# 5-de-7.net
KiCad netlist of a schematic drawn in EAGLE
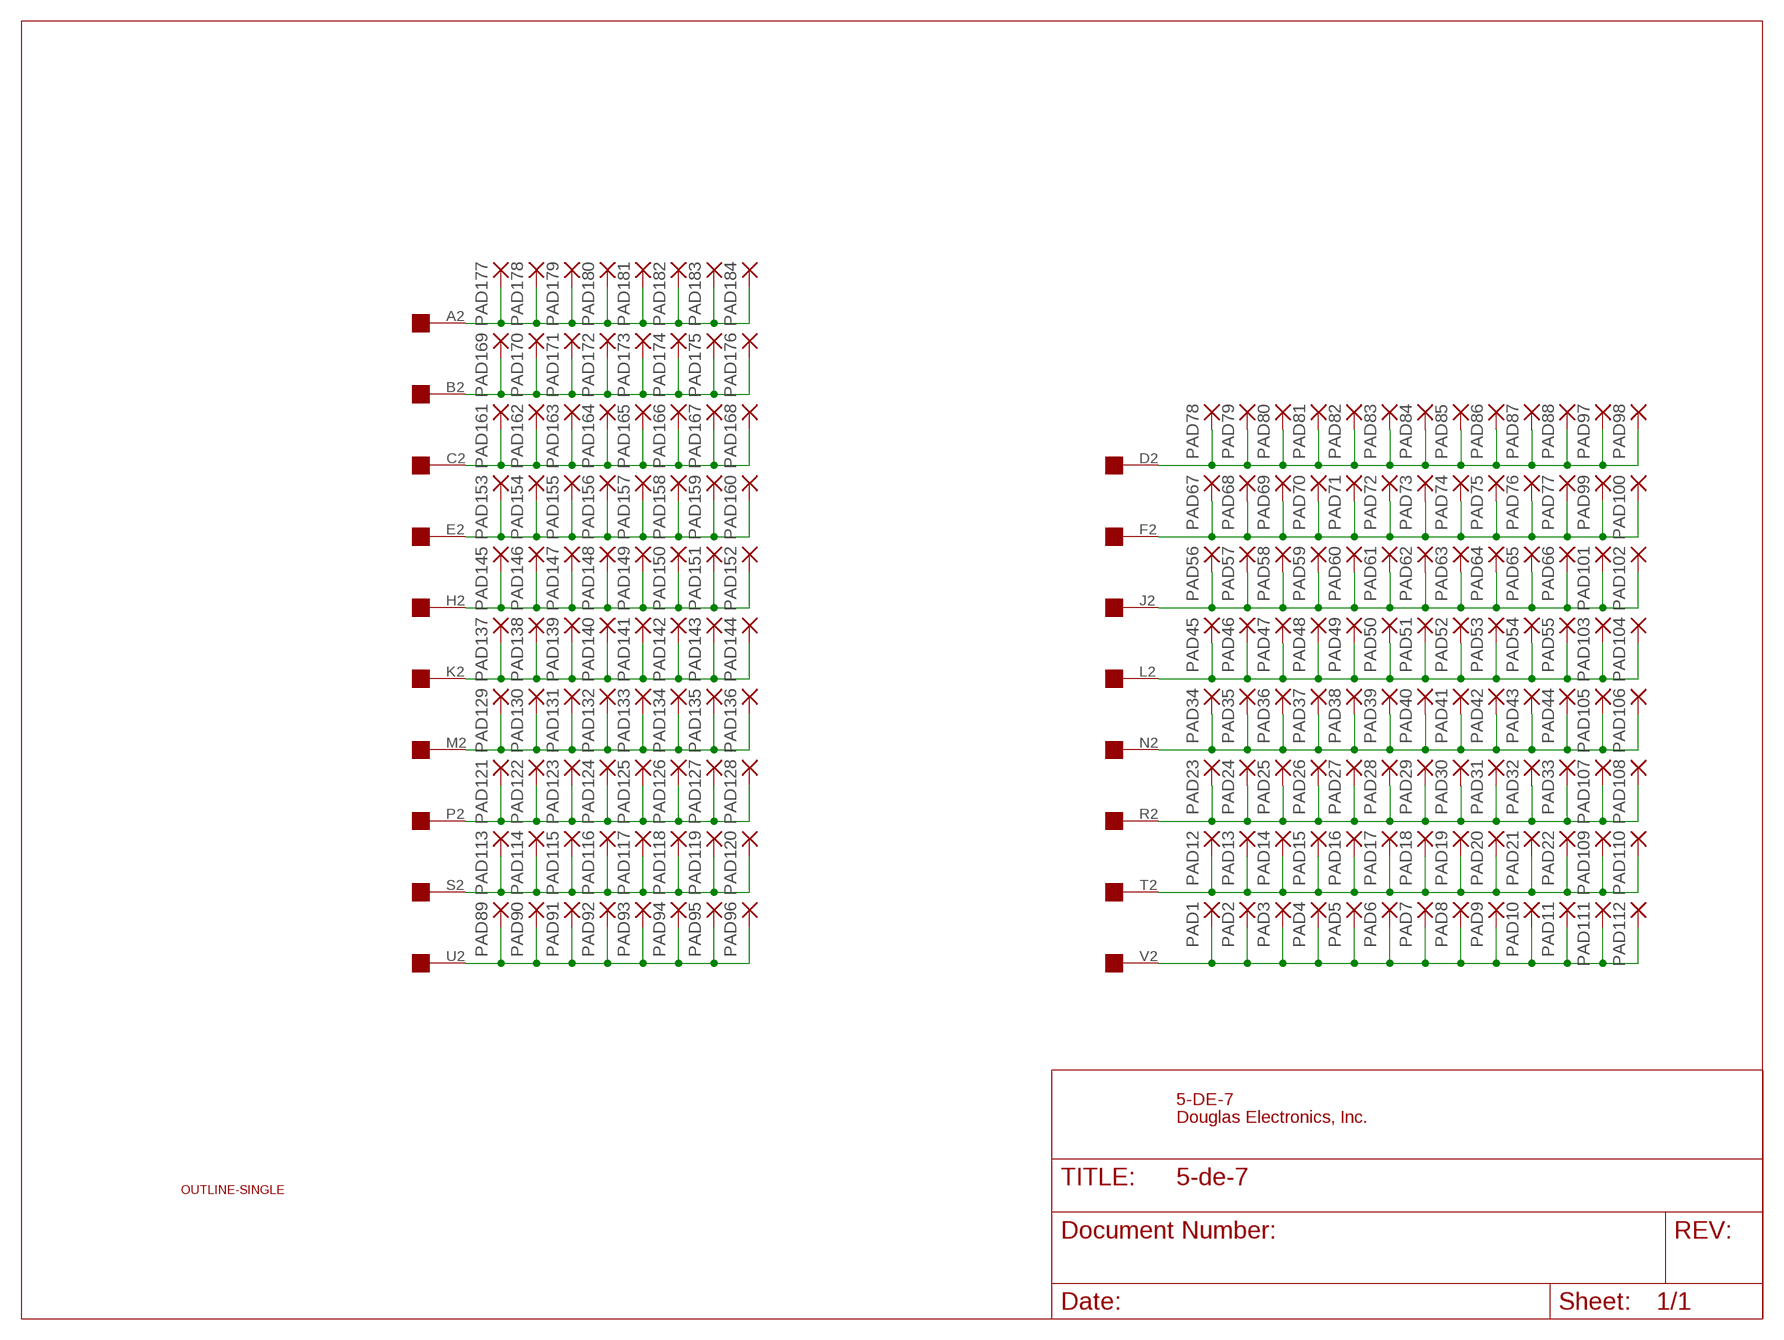
[diagram p0: schematic, sheet 1]

(export (version "E")
  (design (tool "Eeschema 10.0.6"))
  (components
    (comp (ref "PAD1")
      (value "2,54/1,1")
      (footprint "eagle-import:2,54_1,1")
      (libsource (lib "eagle-import") (part "2,54/1,1"))
    )
    (comp (ref "PAD2")
      (value "2,54/1,1")
      (footprint "eagle-import:2,54_1,1")
      (libsource (lib "eagle-import") (part "2,54/1,1"))
    )
    (comp (ref "PAD3")
      (value "2,54/1,1")
      (footprint "eagle-import:2,54_1,1")
      (libsource (lib "eagle-import") (part "2,54/1,1"))
    )
    (comp (ref "PAD4")
      (value "2,54/1,1")
      (footprint "eagle-import:2,54_1,1")
      (libsource (lib "eagle-import") (part "2,54/1,1"))
    )
    (comp (ref "PAD5")
      (value "2,54/1,1")
      (footprint "eagle-import:2,54_1,1")
      (libsource (lib "eagle-import") (part "2,54/1,1"))
    )
    (comp (ref "PAD6")
      (value "2,54/1,1")
      (footprint "eagle-import:2,54_1,1")
      (libsource (lib "eagle-import") (part "2,54/1,1"))
    )
    (comp (ref "PAD7")
      (value "2,54/1,1")
      (footprint "eagle-import:2,54_1,1")
      (libsource (lib "eagle-import") (part "2,54/1,1"))
    )
    (comp (ref "PAD8")
      (value "2,54/1,1")
      (footprint "eagle-import:2,54_1,1")
      (libsource (lib "eagle-import") (part "2,54/1,1"))
    )
    (comp (ref "PAD9")
      (value "2,54/1,1")
      (footprint "eagle-import:2,54_1,1")
      (libsource (lib "eagle-import") (part "2,54/1,1"))
    )
    (comp (ref "PAD10")
      (value "2,54/1,1")
      (footprint "eagle-import:2,54_1,1")
      (libsource (lib "eagle-import") (part "2,54/1,1"))
    )
    (comp (ref "PAD11")
      (value "2,54/1,1")
      (footprint "eagle-import:2,54_1,1")
      (libsource (lib "eagle-import") (part "2,54/1,1"))
    )
    (comp (ref "PAD12")
      (value "2,54/1,1")
      (footprint "eagle-import:2,54_1,1")
      (libsource (lib "eagle-import") (part "2,54/1,1"))
    )
    (comp (ref "PAD13")
      (value "2,54/1,1")
      (footprint "eagle-import:2,54_1,1")
      (libsource (lib "eagle-import") (part "2,54/1,1"))
    )
    (comp (ref "PAD14")
      (value "2,54/1,1")
      (footprint "eagle-import:2,54_1,1")
      (libsource (lib "eagle-import") (part "2,54/1,1"))
    )
    (comp (ref "PAD15")
      (value "2,54/1,1")
      (footprint "eagle-import:2,54_1,1")
      (libsource (lib "eagle-import") (part "2,54/1,1"))
    )
    (comp (ref "PAD16")
      (value "2,54/1,1")
      (footprint "eagle-import:2,54_1,1")
      (libsource (lib "eagle-import") (part "2,54/1,1"))
    )
    (comp (ref "PAD17")
      (value "2,54/1,1")
      (footprint "eagle-import:2,54_1,1")
      (libsource (lib "eagle-import") (part "2,54/1,1"))
    )
    (comp (ref "PAD18")
      (value "2,54/1,1")
      (footprint "eagle-import:2,54_1,1")
      (libsource (lib "eagle-import") (part "2,54/1,1"))
    )
    (comp (ref "PAD19")
      (value "2,54/1,1")
      (footprint "eagle-import:2,54_1,1")
      (libsource (lib "eagle-import") (part "2,54/1,1"))
    )
    (comp (ref "PAD20")
      (value "2,54/1,1")
      (footprint "eagle-import:2,54_1,1")
      (libsource (lib "eagle-import") (part "2,54/1,1"))
    )
    (comp (ref "PAD21")
      (value "2,54/1,1")
      (footprint "eagle-import:2,54_1,1")
      (libsource (lib "eagle-import") (part "2,54/1,1"))
    )
    (comp (ref "PAD22")
      (value "2,54/1,1")
      (footprint "eagle-import:2,54_1,1")
      (libsource (lib "eagle-import") (part "2,54/1,1"))
    )
    (comp (ref "PAD23")
      (value "2,54/1,1")
      (footprint "eagle-import:2,54_1,1")
      (libsource (lib "eagle-import") (part "2,54/1,1"))
    )
    (comp (ref "PAD24")
      (value "2,54/1,1")
      (footprint "eagle-import:2,54_1,1")
      (libsource (lib "eagle-import") (part "2,54/1,1"))
    )
    (comp (ref "PAD25")
      (value "2,54/1,1")
      (footprint "eagle-import:2,54_1,1")
      (libsource (lib "eagle-import") (part "2,54/1,1"))
    )
    (comp (ref "PAD26")
      (value "2,54/1,1")
      (footprint "eagle-import:2,54_1,1")
      (libsource (lib "eagle-import") (part "2,54/1,1"))
    )
    (comp (ref "PAD27")
      (value "2,54/1,1")
      (footprint "eagle-import:2,54_1,1")
      (libsource (lib "eagle-import") (part "2,54/1,1"))
    )
    (comp (ref "PAD28")
      (value "2,54/1,1")
      (footprint "eagle-import:2,54_1,1")
      (libsource (lib "eagle-import") (part "2,54/1,1"))
    )
    (comp (ref "PAD29")
      (value "2,54/1,1")
      (footprint "eagle-import:2,54_1,1")
      (libsource (lib "eagle-import") (part "2,54/1,1"))
    )
    (comp (ref "PAD30")
      (value "2,54/1,1")
      (footprint "eagle-import:2,54_1,1")
      (libsource (lib "eagle-import") (part "2,54/1,1"))
    )
    (comp (ref "PAD31")
      (value "2,54/1,1")
      (footprint "eagle-import:2,54_1,1")
      (libsource (lib "eagle-import") (part "2,54/1,1"))
    )
    (comp (ref "PAD32")
      (value "2,54/1,1")
      (footprint "eagle-import:2,54_1,1")
      (libsource (lib "eagle-import") (part "2,54/1,1"))
    )
    (comp (ref "PAD33")
      (value "2,54/1,1")
      (footprint "eagle-import:2,54_1,1")
      (libsource (lib "eagle-import") (part "2,54/1,1"))
    )
    (comp (ref "PAD34")
      (value "2,54/1,1")
      (footprint "eagle-import:2,54_1,1")
      (libsource (lib "eagle-import") (part "2,54/1,1"))
    )
    (comp (ref "PAD35")
      (value "2,54/1,1")
      (footprint "eagle-import:2,54_1,1")
      (libsource (lib "eagle-import") (part "2,54/1,1"))
    )
    (comp (ref "PAD36")
      (value "2,54/1,1")
      (footprint "eagle-import:2,54_1,1")
      (libsource (lib "eagle-import") (part "2,54/1,1"))
    )
    (comp (ref "PAD37")
      (value "2,54/1,1")
      (footprint "eagle-import:2,54_1,1")
      (libsource (lib "eagle-import") (part "2,54/1,1"))
    )
    (comp (ref "PAD38")
      (value "2,54/1,1")
      (footprint "eagle-import:2,54_1,1")
      (libsource (lib "eagle-import") (part "2,54/1,1"))
    )
    (comp (ref "PAD39")
      (value "2,54/1,1")
      (footprint "eagle-import:2,54_1,1")
      (libsource (lib "eagle-import") (part "2,54/1,1"))
    )
    (comp (ref "PAD40")
      (value "2,54/1,1")
      (footprint "eagle-import:2,54_1,1")
      (libsource (lib "eagle-import") (part "2,54/1,1"))
    )
    (comp (ref "PAD41")
      (value "2,54/1,1")
      (footprint "eagle-import:2,54_1,1")
      (libsource (lib "eagle-import") (part "2,54/1,1"))
    )
    (comp (ref "PAD42")
      (value "2,54/1,1")
      (footprint "eagle-import:2,54_1,1")
      (libsource (lib "eagle-import") (part "2,54/1,1"))
    )
    (comp (ref "PAD43")
      (value "2,54/1,1")
      (footprint "eagle-import:2,54_1,1")
      (libsource (lib "eagle-import") (part "2,54/1,1"))
    )
    (comp (ref "PAD44")
      (value "2,54/1,1")
      (footprint "eagle-import:2,54_1,1")
      (libsource (lib "eagle-import") (part "2,54/1,1"))
    )
    (comp (ref "PAD45")
      (value "2,54/1,1")
      (footprint "eagle-import:2,54_1,1")
      (libsource (lib "eagle-import") (part "2,54/1,1"))
    )
    (comp (ref "PAD46")
      (value "2,54/1,1")
      (footprint "eagle-import:2,54_1,1")
      (libsource (lib "eagle-import") (part "2,54/1,1"))
    )
    (comp (ref "PAD47")
      (value "2,54/1,1")
      (footprint "eagle-import:2,54_1,1")
      (libsource (lib "eagle-import") (part "2,54/1,1"))
    )
    (comp (ref "PAD48")
      (value "2,54/1,1")
      (footprint "eagle-import:2,54_1,1")
      (libsource (lib "eagle-import") (part "2,54/1,1"))
    )
    (comp (ref "PAD49")
      (value "2,54/1,1")
      (footprint "eagle-import:2,54_1,1")
      (libsource (lib "eagle-import") (part "2,54/1,1"))
    )
    (comp (ref "PAD50")
      (value "2,54/1,1")
      (footprint "eagle-import:2,54_1,1")
      (libsource (lib "eagle-import") (part "2,54/1,1"))
    )
    (comp (ref "PAD51")
      (value "2,54/1,1")
      (footprint "eagle-import:2,54_1,1")
      (libsource (lib "eagle-import") (part "2,54/1,1"))
    )
    (comp (ref "PAD52")
      (value "2,54/1,1")
      (footprint "eagle-import:2,54_1,1")
      (libsource (lib "eagle-import") (part "2,54/1,1"))
    )
    (comp (ref "PAD53")
      (value "2,54/1,1")
      (footprint "eagle-import:2,54_1,1")
      (libsource (lib "eagle-import") (part "2,54/1,1"))
    )
    (comp (ref "PAD54")
      (value "2,54/1,1")
      (footprint "eagle-import:2,54_1,1")
      (libsource (lib "eagle-import") (part "2,54/1,1"))
    )
    (comp (ref "PAD55")
      (value "2,54/1,1")
      (footprint "eagle-import:2,54_1,1")
      (libsource (lib "eagle-import") (part "2,54/1,1"))
    )
    (comp (ref "PAD56")
      (value "2,54/1,1")
      (footprint "eagle-import:2,54_1,1")
      (libsource (lib "eagle-import") (part "2,54/1,1"))
    )
    (comp (ref "PAD57")
      (value "2,54/1,1")
      (footprint "eagle-import:2,54_1,1")
      (libsource (lib "eagle-import") (part "2,54/1,1"))
    )
    (comp (ref "PAD58")
      (value "2,54/1,1")
      (footprint "eagle-import:2,54_1,1")
      (libsource (lib "eagle-import") (part "2,54/1,1"))
    )
    (comp (ref "PAD59")
      (value "2,54/1,1")
      (footprint "eagle-import:2,54_1,1")
      (libsource (lib "eagle-import") (part "2,54/1,1"))
    )
    (comp (ref "PAD60")
      (value "2,54/1,1")
      (footprint "eagle-import:2,54_1,1")
      (libsource (lib "eagle-import") (part "2,54/1,1"))
    )
    (comp (ref "PAD61")
      (value "2,54/1,1")
      (footprint "eagle-import:2,54_1,1")
      (libsource (lib "eagle-import") (part "2,54/1,1"))
    )
    (comp (ref "PAD62")
      (value "2,54/1,1")
      (footprint "eagle-import:2,54_1,1")
      (libsource (lib "eagle-import") (part "2,54/1,1"))
    )
    (comp (ref "PAD63")
      (value "2,54/1,1")
      (footprint "eagle-import:2,54_1,1")
      (libsource (lib "eagle-import") (part "2,54/1,1"))
    )
    (comp (ref "PAD64")
      (value "2,54/1,1")
      (footprint "eagle-import:2,54_1,1")
      (libsource (lib "eagle-import") (part "2,54/1,1"))
    )
    (comp (ref "PAD65")
      (value "2,54/1,1")
      (footprint "eagle-import:2,54_1,1")
      (libsource (lib "eagle-import") (part "2,54/1,1"))
    )
    (comp (ref "PAD66")
      (value "2,54/1,1")
      (footprint "eagle-import:2,54_1,1")
      (libsource (lib "eagle-import") (part "2,54/1,1"))
    )
    (comp (ref "PAD67")
      (value "2,54/1,1")
      (footprint "eagle-import:2,54_1,1")
      (libsource (lib "eagle-import") (part "2,54/1,1"))
    )
    (comp (ref "PAD68")
      (value "2,54/1,1")
      (footprint "eagle-import:2,54_1,1")
      (libsource (lib "eagle-import") (part "2,54/1,1"))
    )
    (comp (ref "PAD69")
      (value "2,54/1,1")
      (footprint "eagle-import:2,54_1,1")
      (libsource (lib "eagle-import") (part "2,54/1,1"))
    )
    (comp (ref "PAD70")
      (value "2,54/1,1")
      (footprint "eagle-import:2,54_1,1")
      (libsource (lib "eagle-import") (part "2,54/1,1"))
    )
    (comp (ref "PAD71")
      (value "2,54/1,1")
      (footprint "eagle-import:2,54_1,1")
      (libsource (lib "eagle-import") (part "2,54/1,1"))
    )
    (comp (ref "PAD72")
      (value "2,54/1,1")
      (footprint "eagle-import:2,54_1,1")
      (libsource (lib "eagle-import") (part "2,54/1,1"))
    )
    (comp (ref "PAD73")
      (value "2,54/1,1")
      (footprint "eagle-import:2,54_1,1")
      (libsource (lib "eagle-import") (part "2,54/1,1"))
    )
    (comp (ref "PAD74")
      (value "2,54/1,1")
      (footprint "eagle-import:2,54_1,1")
      (libsource (lib "eagle-import") (part "2,54/1,1"))
    )
    (comp (ref "PAD75")
      (value "2,54/1,1")
      (footprint "eagle-import:2,54_1,1")
      (libsource (lib "eagle-import") (part "2,54/1,1"))
    )
    (comp (ref "PAD76")
      (value "2,54/1,1")
      (footprint "eagle-import:2,54_1,1")
      (libsource (lib "eagle-import") (part "2,54/1,1"))
    )
    (comp (ref "PAD77")
      (value "2,54/1,1")
      (footprint "eagle-import:2,54_1,1")
      (libsource (lib "eagle-import") (part "2,54/1,1"))
    )
    (comp (ref "PAD78")
      (value "2,54/1,1")
      (footprint "eagle-import:2,54_1,1")
      (libsource (lib "eagle-import") (part "2,54/1,1"))
    )
    (comp (ref "PAD79")
      (value "2,54/1,1")
      (footprint "eagle-import:2,54_1,1")
      (libsource (lib "eagle-import") (part "2,54/1,1"))
    )
    (comp (ref "PAD80")
      (value "2,54/1,1")
      (footprint "eagle-import:2,54_1,1")
      (libsource (lib "eagle-import") (part "2,54/1,1"))
    )
    (comp (ref "PAD81")
      (value "2,54/1,1")
      (footprint "eagle-import:2,54_1,1")
      (libsource (lib "eagle-import") (part "2,54/1,1"))
    )
    (comp (ref "PAD82")
      (value "2,54/1,1")
      (footprint "eagle-import:2,54_1,1")
      (libsource (lib "eagle-import") (part "2,54/1,1"))
    )
    (comp (ref "PAD83")
      (value "2,54/1,1")
      (footprint "eagle-import:2,54_1,1")
      (libsource (lib "eagle-import") (part "2,54/1,1"))
    )
    (comp (ref "PAD84")
      (value "2,54/1,1")
      (footprint "eagle-import:2,54_1,1")
      (libsource (lib "eagle-import") (part "2,54/1,1"))
    )
    (comp (ref "PAD85")
      (value "2,54/1,1")
      (footprint "eagle-import:2,54_1,1")
      (libsource (lib "eagle-import") (part "2,54/1,1"))
    )
    (comp (ref "PAD86")
      (value "2,54/1,1")
      (footprint "eagle-import:2,54_1,1")
      (libsource (lib "eagle-import") (part "2,54/1,1"))
    )
    (comp (ref "PAD87")
      (value "2,54/1,1")
      (footprint "eagle-import:2,54_1,1")
      (libsource (lib "eagle-import") (part "2,54/1,1"))
    )
    (comp (ref "PAD88")
      (value "2,54/1,1")
      (footprint "eagle-import:2,54_1,1")
      (libsource (lib "eagle-import") (part "2,54/1,1"))
    )
    (comp (ref "PAD89")
      (value "2,54/1,1")
      (footprint "eagle-import:2,54_1,1")
      (libsource (lib "eagle-import") (part "2,54/1,1"))
    )
    (comp (ref "PAD90")
      (value "2,54/1,1")
      (footprint "eagle-import:2,54_1,1")
      (libsource (lib "eagle-import") (part "2,54/1,1"))
    )
    (comp (ref "PAD91")
      (value "2,54/1,1")
      (footprint "eagle-import:2,54_1,1")
      (libsource (lib "eagle-import") (part "2,54/1,1"))
    )
    (comp (ref "PAD92")
      (value "2,54/1,1")
      (footprint "eagle-import:2,54_1,1")
      (libsource (lib "eagle-import") (part "2,54/1,1"))
    )
    (comp (ref "PAD93")
      (value "2,54/1,1")
      (footprint "eagle-import:2,54_1,1")
      (libsource (lib "eagle-import") (part "2,54/1,1"))
    )
    (comp (ref "PAD94")
      (value "2,54/1,1")
      (footprint "eagle-import:2,54_1,1")
      (libsource (lib "eagle-import") (part "2,54/1,1"))
    )
    (comp (ref "PAD95")
      (value "2,54/1,1")
      (footprint "eagle-import:2,54_1,1")
      (libsource (lib "eagle-import") (part "2,54/1,1"))
    )
    (comp (ref "PAD96")
      (value "2,54/1,1")
      (footprint "eagle-import:2,54_1,1")
      (libsource (lib "eagle-import") (part "2,54/1,1"))
    )
    (comp (ref "PAD97")
      (value "2,54/1,1")
      (footprint "eagle-import:2,54_1,1")
      (libsource (lib "eagle-import") (part "2,54/1,1"))
    )
    (comp (ref "PAD98")
      (value "2,54/1,1")
      (footprint "eagle-import:2,54_1,1")
      (libsource (lib "eagle-import") (part "2,54/1,1"))
    )
    (comp (ref "PAD99")
      (value "2,54/1,1")
      (footprint "eagle-import:2,54_1,1")
      (libsource (lib "eagle-import") (part "2,54/1,1"))
    )
    (comp (ref "PAD100")
      (value "2,54/1,1")
      (footprint "eagle-import:2,54_1,1")
      (libsource (lib "eagle-import") (part "2,54/1,1"))
    )
    (comp (ref "PAD101")
      (value "2,54/1,1")
      (footprint "eagle-import:2,54_1,1")
      (libsource (lib "eagle-import") (part "2,54/1,1"))
    )
    (comp (ref "PAD102")
      (value "2,54/1,1")
      (footprint "eagle-import:2,54_1,1")
      (libsource (lib "eagle-import") (part "2,54/1,1"))
    )
    (comp (ref "PAD103")
      (value "2,54/1,1")
      (footprint "eagle-import:2,54_1,1")
      (libsource (lib "eagle-import") (part "2,54/1,1"))
    )
    (comp (ref "PAD104")
      (value "2,54/1,1")
      (footprint "eagle-import:2,54_1,1")
      (libsource (lib "eagle-import") (part "2,54/1,1"))
    )
    (comp (ref "PAD105")
      (value "2,54/1,1")
      (footprint "eagle-import:2,54_1,1")
      (libsource (lib "eagle-import") (part "2,54/1,1"))
    )
    (comp (ref "PAD106")
      (value "2,54/1,1")
      (footprint "eagle-import:2,54_1,1")
      (libsource (lib "eagle-import") (part "2,54/1,1"))
    )
    (comp (ref "PAD107")
      (value "2,54/1,1")
      (footprint "eagle-import:2,54_1,1")
      (libsource (lib "eagle-import") (part "2,54/1,1"))
    )
    (comp (ref "PAD108")
      (value "2,54/1,1")
      (footprint "eagle-import:2,54_1,1")
      (libsource (lib "eagle-import") (part "2,54/1,1"))
    )
    (comp (ref "PAD109")
      (value "2,54/1,1")
      (footprint "eagle-import:2,54_1,1")
      (libsource (lib "eagle-import") (part "2,54/1,1"))
    )
    (comp (ref "PAD110")
      (value "2,54/1,1")
      (footprint "eagle-import:2,54_1,1")
      (libsource (lib "eagle-import") (part "2,54/1,1"))
    )
    (comp (ref "PAD111")
      (value "2,54/1,1")
      (footprint "eagle-import:2,54_1,1")
      (libsource (lib "eagle-import") (part "2,54/1,1"))
    )
    (comp (ref "PAD112")
      (value "2,54/1,1")
      (footprint "eagle-import:2,54_1,1")
      (libsource (lib "eagle-import") (part "2,54/1,1"))
    )
    (comp (ref "PAD113")
      (value "2,54/1,1")
      (footprint "eagle-import:2,54_1,1")
      (libsource (lib "eagle-import") (part "2,54/1,1"))
    )
    (comp (ref "PAD114")
      (value "2,54/1,1")
      (footprint "eagle-import:2,54_1,1")
      (libsource (lib "eagle-import") (part "2,54/1,1"))
    )
    (comp (ref "PAD115")
      (value "2,54/1,1")
      (footprint "eagle-import:2,54_1,1")
      (libsource (lib "eagle-import") (part "2,54/1,1"))
    )
    (comp (ref "PAD116")
      (value "2,54/1,1")
      (footprint "eagle-import:2,54_1,1")
      (libsource (lib "eagle-import") (part "2,54/1,1"))
    )
    (comp (ref "PAD117")
      (value "2,54/1,1")
      (footprint "eagle-import:2,54_1,1")
      (libsource (lib "eagle-import") (part "2,54/1,1"))
    )
    (comp (ref "PAD118")
      (value "2,54/1,1")
      (footprint "eagle-import:2,54_1,1")
      (libsource (lib "eagle-import") (part "2,54/1,1"))
    )
    (comp (ref "PAD119")
      (value "2,54/1,1")
      (footprint "eagle-import:2,54_1,1")
      (libsource (lib "eagle-import") (part "2,54/1,1"))
    )
    (comp (ref "PAD120")
      (value "2,54/1,1")
      (footprint "eagle-import:2,54_1,1")
      (libsource (lib "eagle-import") (part "2,54/1,1"))
    )
    (comp (ref "PAD121")
      (value "2,54/1,1")
      (footprint "eagle-import:2,54_1,1")
      (libsource (lib "eagle-import") (part "2,54/1,1"))
    )
    (comp (ref "PAD122")
      (value "2,54/1,1")
      (footprint "eagle-import:2,54_1,1")
      (libsource (lib "eagle-import") (part "2,54/1,1"))
    )
    (comp (ref "PAD123")
      (value "2,54/1,1")
      (footprint "eagle-import:2,54_1,1")
      (libsource (lib "eagle-import") (part "2,54/1,1"))
    )
    (comp (ref "PAD124")
      (value "2,54/1,1")
      (footprint "eagle-import:2,54_1,1")
      (libsource (lib "eagle-import") (part "2,54/1,1"))
    )
    (comp (ref "PAD125")
      (value "2,54/1,1")
      (footprint "eagle-import:2,54_1,1")
      (libsource (lib "eagle-import") (part "2,54/1,1"))
    )
    (comp (ref "PAD126")
      (value "2,54/1,1")
      (footprint "eagle-import:2,54_1,1")
      (libsource (lib "eagle-import") (part "2,54/1,1"))
    )
    (comp (ref "PAD127")
      (value "2,54/1,1")
      (footprint "eagle-import:2,54_1,1")
      (libsource (lib "eagle-import") (part "2,54/1,1"))
    )
    (comp (ref "PAD128")
      (value "2,54/1,1")
      (footprint "eagle-import:2,54_1,1")
      (libsource (lib "eagle-import") (part "2,54/1,1"))
    )
    (comp (ref "PAD129")
      (value "2,54/1,1")
      (footprint "eagle-import:2,54_1,1")
      (libsource (lib "eagle-import") (part "2,54/1,1"))
    )
    (comp (ref "PAD130")
      (value "2,54/1,1")
      (footprint "eagle-import:2,54_1,1")
      (libsource (lib "eagle-import") (part "2,54/1,1"))
    )
    (comp (ref "PAD131")
      (value "2,54/1,1")
      (footprint "eagle-import:2,54_1,1")
      (libsource (lib "eagle-import") (part "2,54/1,1"))
    )
    (comp (ref "PAD132")
      (value "2,54/1,1")
      (footprint "eagle-import:2,54_1,1")
      (libsource (lib "eagle-import") (part "2,54/1,1"))
    )
    (comp (ref "PAD133")
      (value "2,54/1,1")
      (footprint "eagle-import:2,54_1,1")
      (libsource (lib "eagle-import") (part "2,54/1,1"))
    )
    (comp (ref "PAD134")
      (value "2,54/1,1")
      (footprint "eagle-import:2,54_1,1")
      (libsource (lib "eagle-import") (part "2,54/1,1"))
    )
    (comp (ref "PAD135")
      (value "2,54/1,1")
      (footprint "eagle-import:2,54_1,1")
      (libsource (lib "eagle-import") (part "2,54/1,1"))
    )
    (comp (ref "PAD136")
      (value "2,54/1,1")
      (footprint "eagle-import:2,54_1,1")
      (libsource (lib "eagle-import") (part "2,54/1,1"))
    )
    (comp (ref "PAD137")
      (value "2,54/1,1")
      (footprint "eagle-import:2,54_1,1")
      (libsource (lib "eagle-import") (part "2,54/1,1"))
    )
    (comp (ref "PAD138")
      (value "2,54/1,1")
      (footprint "eagle-import:2,54_1,1")
      (libsource (lib "eagle-import") (part "2,54/1,1"))
    )
    (comp (ref "PAD139")
      (value "2,54/1,1")
      (footprint "eagle-import:2,54_1,1")
      (libsource (lib "eagle-import") (part "2,54/1,1"))
    )
    (comp (ref "PAD140")
      (value "2,54/1,1")
      (footprint "eagle-import:2,54_1,1")
      (libsource (lib "eagle-import") (part "2,54/1,1"))
    )
    (comp (ref "PAD141")
      (value "2,54/1,1")
      (footprint "eagle-import:2,54_1,1")
      (libsource (lib "eagle-import") (part "2,54/1,1"))
    )
    (comp (ref "PAD142")
      (value "2,54/1,1")
      (footprint "eagle-import:2,54_1,1")
      (libsource (lib "eagle-import") (part "2,54/1,1"))
    )
    (comp (ref "PAD143")
      (value "2,54/1,1")
      (footprint "eagle-import:2,54_1,1")
      (libsource (lib "eagle-import") (part "2,54/1,1"))
    )
    (comp (ref "PAD144")
      (value "2,54/1,1")
      (footprint "eagle-import:2,54_1,1")
      (libsource (lib "eagle-import") (part "2,54/1,1"))
    )
    (comp (ref "PAD145")
      (value "2,54/1,1")
      (footprint "eagle-import:2,54_1,1")
      (libsource (lib "eagle-import") (part "2,54/1,1"))
    )
    (comp (ref "PAD146")
      (value "2,54/1,1")
      (footprint "eagle-import:2,54_1,1")
      (libsource (lib "eagle-import") (part "2,54/1,1"))
    )
    (comp (ref "PAD147")
      (value "2,54/1,1")
      (footprint "eagle-import:2,54_1,1")
      (libsource (lib "eagle-import") (part "2,54/1,1"))
    )
    (comp (ref "PAD148")
      (value "2,54/1,1")
      (footprint "eagle-import:2,54_1,1")
      (libsource (lib "eagle-import") (part "2,54/1,1"))
    )
    (comp (ref "PAD149")
      (value "2,54/1,1")
      (footprint "eagle-import:2,54_1,1")
      (libsource (lib "eagle-import") (part "2,54/1,1"))
    )
    (comp (ref "PAD150")
      (value "2,54/1,1")
      (footprint "eagle-import:2,54_1,1")
      (libsource (lib "eagle-import") (part "2,54/1,1"))
    )
    (comp (ref "PAD151")
      (value "2,54/1,1")
      (footprint "eagle-import:2,54_1,1")
      (libsource (lib "eagle-import") (part "2,54/1,1"))
    )
    (comp (ref "PAD152")
      (value "2,54/1,1")
      (footprint "eagle-import:2,54_1,1")
      (libsource (lib "eagle-import") (part "2,54/1,1"))
    )
    (comp (ref "PAD153")
      (value "2,54/1,1")
      (footprint "eagle-import:2,54_1,1")
      (libsource (lib "eagle-import") (part "2,54/1,1"))
    )
    (comp (ref "PAD154")
      (value "2,54/1,1")
      (footprint "eagle-import:2,54_1,1")
      (libsource (lib "eagle-import") (part "2,54/1,1"))
    )
    (comp (ref "PAD155")
      (value "2,54/1,1")
      (footprint "eagle-import:2,54_1,1")
      (libsource (lib "eagle-import") (part "2,54/1,1"))
    )
    (comp (ref "PAD156")
      (value "2,54/1,1")
      (footprint "eagle-import:2,54_1,1")
      (libsource (lib "eagle-import") (part "2,54/1,1"))
    )
    (comp (ref "PAD157")
      (value "2,54/1,1")
      (footprint "eagle-import:2,54_1,1")
      (libsource (lib "eagle-import") (part "2,54/1,1"))
    )
    (comp (ref "PAD158")
      (value "2,54/1,1")
      (footprint "eagle-import:2,54_1,1")
      (libsource (lib "eagle-import") (part "2,54/1,1"))
    )
    (comp (ref "PAD159")
      (value "2,54/1,1")
      (footprint "eagle-import:2,54_1,1")
      (libsource (lib "eagle-import") (part "2,54/1,1"))
    )
    (comp (ref "PAD160")
      (value "2,54/1,1")
      (footprint "eagle-import:2,54_1,1")
      (libsource (lib "eagle-import") (part "2,54/1,1"))
    )
    (comp (ref "PAD161")
      (value "2,54/1,1")
      (footprint "eagle-import:2,54_1,1")
      (libsource (lib "eagle-import") (part "2,54/1,1"))
    )
    (comp (ref "PAD162")
      (value "2,54/1,1")
      (footprint "eagle-import:2,54_1,1")
      (libsource (lib "eagle-import") (part "2,54/1,1"))
    )
    (comp (ref "PAD163")
      (value "2,54/1,1")
      (footprint "eagle-import:2,54_1,1")
      (libsource (lib "eagle-import") (part "2,54/1,1"))
    )
    (comp (ref "PAD164")
      (value "2,54/1,1")
      (footprint "eagle-import:2,54_1,1")
      (libsource (lib "eagle-import") (part "2,54/1,1"))
    )
    (comp (ref "PAD165")
      (value "2,54/1,1")
      (footprint "eagle-import:2,54_1,1")
      (libsource (lib "eagle-import") (part "2,54/1,1"))
    )
    (comp (ref "PAD166")
      (value "2,54/1,1")
      (footprint "eagle-import:2,54_1,1")
      (libsource (lib "eagle-import") (part "2,54/1,1"))
    )
    (comp (ref "PAD167")
      (value "2,54/1,1")
      (footprint "eagle-import:2,54_1,1")
      (libsource (lib "eagle-import") (part "2,54/1,1"))
    )
    (comp (ref "PAD168")
      (value "2,54/1,1")
      (footprint "eagle-import:2,54_1,1")
      (libsource (lib "eagle-import") (part "2,54/1,1"))
    )
    (comp (ref "PAD169")
      (value "2,54/1,1")
      (footprint "eagle-import:2,54_1,1")
      (libsource (lib "eagle-import") (part "2,54/1,1"))
    )
    (comp (ref "PAD170")
      (value "2,54/1,1")
      (footprint "eagle-import:2,54_1,1")
      (libsource (lib "eagle-import") (part "2,54/1,1"))
    )
    (comp (ref "PAD171")
      (value "2,54/1,1")
      (footprint "eagle-import:2,54_1,1")
      (libsource (lib "eagle-import") (part "2,54/1,1"))
    )
    (comp (ref "PAD172")
      (value "2,54/1,1")
      (footprint "eagle-import:2,54_1,1")
      (libsource (lib "eagle-import") (part "2,54/1,1"))
    )
    (comp (ref "PAD173")
      (value "2,54/1,1")
      (footprint "eagle-import:2,54_1,1")
      (libsource (lib "eagle-import") (part "2,54/1,1"))
    )
    (comp (ref "PAD174")
      (value "2,54/1,1")
      (footprint "eagle-import:2,54_1,1")
      (libsource (lib "eagle-import") (part "2,54/1,1"))
    )
    (comp (ref "PAD175")
      (value "2,54/1,1")
      (footprint "eagle-import:2,54_1,1")
      (libsource (lib "eagle-import") (part "2,54/1,1"))
    )
    (comp (ref "PAD176")
      (value "2,54/1,1")
      (footprint "eagle-import:2,54_1,1")
      (libsource (lib "eagle-import") (part "2,54/1,1"))
    )
    (comp (ref "PAD177")
      (value "2,54/1,1")
      (footprint "eagle-import:2,54_1,1")
      (libsource (lib "eagle-import") (part "2,54/1,1"))
    )
    (comp (ref "PAD178")
      (value "2,54/1,1")
      (footprint "eagle-import:2,54_1,1")
      (libsource (lib "eagle-import") (part "2,54/1,1"))
    )
    (comp (ref "PAD179")
      (value "2,54/1,1")
      (footprint "eagle-import:2,54_1,1")
      (libsource (lib "eagle-import") (part "2,54/1,1"))
    )
    (comp (ref "PAD180")
      (value "2,54/1,1")
      (footprint "eagle-import:2,54_1,1")
      (libsource (lib "eagle-import") (part "2,54/1,1"))
    )
    (comp (ref "PAD181")
      (value "2,54/1,1")
      (footprint "eagle-import:2,54_1,1")
      (libsource (lib "eagle-import") (part "2,54/1,1"))
    )
    (comp (ref "PAD182")
      (value "2,54/1,1")
      (footprint "eagle-import:2,54_1,1")
      (libsource (lib "eagle-import") (part "2,54/1,1"))
    )
    (comp (ref "PAD183")
      (value "2,54/1,1")
      (footprint "eagle-import:2,54_1,1")
      (libsource (lib "eagle-import") (part "2,54/1,1"))
    )
    (comp (ref "PAD184")
      (value "2,54/1,1")
      (footprint "eagle-import:2,54_1,1")
      (libsource (lib "eagle-import") (part "2,54/1,1"))
    )
    (comp (ref "U$2")
      (value "OUTLINE-SINGLE")
      (footprint "eagle-import:SINGLE")
      (libsource (lib "eagle-import") (part "OUTLINE-SINGLE"))
    )
    (comp (ref "U$3")
      (value "EDGE-1")
      (footprint "eagle-import:EDGE-CON1")
      (libsource (lib "eagle-import") (part "EDGE-1"))
    )
  )
  (nets
    (net (code "1") (name "Net-(PAD1-P)") (class "Default")
      (node (ref "PAD1") (pin "1") (pinfunction "P_1") (pintype "passive"))
      (node (ref "PAD10") (pin "1") (pinfunction "P_1") (pintype "passive"))
      (node (ref "PAD11") (pin "1") (pinfunction "P_1") (pintype "passive"))
      (node (ref "PAD111") (pin "1") (pinfunction "P_1") (pintype "passive"))
      (node (ref "PAD112") (pin "1") (pinfunction "P_1") (pintype "passive"))
      (node (ref "PAD2") (pin "1") (pinfunction "P_1") (pintype "passive"))
      (node (ref "PAD3") (pin "1") (pinfunction "P_1") (pintype "passive"))
      (node (ref "PAD4") (pin "1") (pinfunction "P_1") (pintype "passive"))
      (node (ref "PAD5") (pin "1") (pinfunction "P_1") (pintype "passive"))
      (node (ref "PAD6") (pin "1") (pinfunction "P_1") (pintype "passive"))
      (node (ref "PAD7") (pin "1") (pinfunction "P_1") (pintype "passive"))
      (node (ref "PAD8") (pin "1") (pinfunction "P_1") (pintype "passive"))
      (node (ref "PAD9") (pin "1") (pinfunction "P_1") (pintype "passive"))
      (node (ref "U$3") (pin "V2") (pinfunction "1_V2") (pintype "bidirectional"))
    )
    (net (code "2") (name "Net-(PAD78-P)") (class "Default")
      (node (ref "PAD78") (pin "1") (pinfunction "P_1") (pintype "passive"))
      (node (ref "PAD79") (pin "1") (pinfunction "P_1") (pintype "passive"))
      (node (ref "PAD80") (pin "1") (pinfunction "P_1") (pintype "passive"))
      (node (ref "PAD81") (pin "1") (pinfunction "P_1") (pintype "passive"))
      (node (ref "PAD82") (pin "1") (pinfunction "P_1") (pintype "passive"))
      (node (ref "PAD83") (pin "1") (pinfunction "P_1") (pintype "passive"))
      (node (ref "PAD84") (pin "1") (pinfunction "P_1") (pintype "passive"))
      (node (ref "PAD85") (pin "1") (pinfunction "P_1") (pintype "passive"))
      (node (ref "PAD86") (pin "1") (pinfunction "P_1") (pintype "passive"))
      (node (ref "PAD87") (pin "1") (pinfunction "P_1") (pintype "passive"))
      (node (ref "PAD88") (pin "1") (pinfunction "P_1") (pintype "passive"))
      (node (ref "PAD97") (pin "1") (pinfunction "P_1") (pintype "passive"))
      (node (ref "PAD98") (pin "1") (pinfunction "P_1") (pintype "passive"))
      (node (ref "U$3") (pin "D2") (pinfunction "1_D2") (pintype "bidirectional"))
    )
    (net (code "3") (name "Net-(PAD89-P)") (class "Default")
      (node (ref "PAD89") (pin "1") (pinfunction "P_1") (pintype "passive"))
      (node (ref "PAD90") (pin "1") (pinfunction "P_1") (pintype "passive"))
      (node (ref "PAD91") (pin "1") (pinfunction "P_1") (pintype "passive"))
      (node (ref "PAD92") (pin "1") (pinfunction "P_1") (pintype "passive"))
      (node (ref "PAD93") (pin "1") (pinfunction "P_1") (pintype "passive"))
      (node (ref "PAD94") (pin "1") (pinfunction "P_1") (pintype "passive"))
      (node (ref "PAD95") (pin "1") (pinfunction "P_1") (pintype "passive"))
      (node (ref "PAD96") (pin "1") (pinfunction "P_1") (pintype "passive"))
      (node (ref "U$3") (pin "U2") (pinfunction "1_U2") (pintype "bidirectional"))
    )
    (net (code "4") (name "Net-(PAD100-P)") (class "Default")
      (node (ref "PAD100") (pin "1") (pinfunction "P_1") (pintype "passive"))
      (node (ref "PAD67") (pin "1") (pinfunction "P_1") (pintype "passive"))
      (node (ref "PAD68") (pin "1") (pinfunction "P_1") (pintype "passive"))
      (node (ref "PAD69") (pin "1") (pinfunction "P_1") (pintype "passive"))
      (node (ref "PAD70") (pin "1") (pinfunction "P_1") (pintype "passive"))
      (node (ref "PAD71") (pin "1") (pinfunction "P_1") (pintype "passive"))
      (node (ref "PAD72") (pin "1") (pinfunction "P_1") (pintype "passive"))
      (node (ref "PAD73") (pin "1") (pinfunction "P_1") (pintype "passive"))
      (node (ref "PAD74") (pin "1") (pinfunction "P_1") (pintype "passive"))
      (node (ref "PAD75") (pin "1") (pinfunction "P_1") (pintype "passive"))
      (node (ref "PAD76") (pin "1") (pinfunction "P_1") (pintype "passive"))
      (node (ref "PAD77") (pin "1") (pinfunction "P_1") (pintype "passive"))
      (node (ref "PAD99") (pin "1") (pinfunction "P_1") (pintype "passive"))
      (node (ref "U$3") (pin "F2") (pinfunction "1_F2") (pintype "bidirectional"))
    )
    (net (code "5") (name "Net-(PAD101-P)") (class "Default")
      (node (ref "PAD101") (pin "1") (pinfunction "P_1") (pintype "passive"))
      (node (ref "PAD102") (pin "1") (pinfunction "P_1") (pintype "passive"))
      (node (ref "PAD56") (pin "1") (pinfunction "P_1") (pintype "passive"))
      (node (ref "PAD57") (pin "1") (pinfunction "P_1") (pintype "passive"))
      (node (ref "PAD58") (pin "1") (pinfunction "P_1") (pintype "passive"))
      (node (ref "PAD59") (pin "1") (pinfunction "P_1") (pintype "passive"))
      (node (ref "PAD60") (pin "1") (pinfunction "P_1") (pintype "passive"))
      (node (ref "PAD61") (pin "1") (pinfunction "P_1") (pintype "passive"))
      (node (ref "PAD62") (pin "1") (pinfunction "P_1") (pintype "passive"))
      (node (ref "PAD63") (pin "1") (pinfunction "P_1") (pintype "passive"))
      (node (ref "PAD64") (pin "1") (pinfunction "P_1") (pintype "passive"))
      (node (ref "PAD65") (pin "1") (pinfunction "P_1") (pintype "passive"))
      (node (ref "PAD66") (pin "1") (pinfunction "P_1") (pintype "passive"))
      (node (ref "U$3") (pin "J2") (pinfunction "1_J2") (pintype "bidirectional"))
    )
    (net (code "6") (name "Net-(PAD103-P)") (class "Default")
      (node (ref "PAD103") (pin "1") (pinfunction "P_1") (pintype "passive"))
      (node (ref "PAD104") (pin "1") (pinfunction "P_1") (pintype "passive"))
      (node (ref "PAD45") (pin "1") (pinfunction "P_1") (pintype "passive"))
      (node (ref "PAD46") (pin "1") (pinfunction "P_1") (pintype "passive"))
      (node (ref "PAD47") (pin "1") (pinfunction "P_1") (pintype "passive"))
      (node (ref "PAD48") (pin "1") (pinfunction "P_1") (pintype "passive"))
      (node (ref "PAD49") (pin "1") (pinfunction "P_1") (pintype "passive"))
      (node (ref "PAD50") (pin "1") (pinfunction "P_1") (pintype "passive"))
      (node (ref "PAD51") (pin "1") (pinfunction "P_1") (pintype "passive"))
      (node (ref "PAD52") (pin "1") (pinfunction "P_1") (pintype "passive"))
      (node (ref "PAD53") (pin "1") (pinfunction "P_1") (pintype "passive"))
      (node (ref "PAD54") (pin "1") (pinfunction "P_1") (pintype "passive"))
      (node (ref "PAD55") (pin "1") (pinfunction "P_1") (pintype "passive"))
      (node (ref "U$3") (pin "L2") (pinfunction "1_L2") (pintype "bidirectional"))
    )
    (net (code "7") (name "Net-(PAD105-P)") (class "Default")
      (node (ref "PAD105") (pin "1") (pinfunction "P_1") (pintype "passive"))
      (node (ref "PAD106") (pin "1") (pinfunction "P_1") (pintype "passive"))
      (node (ref "PAD34") (pin "1") (pinfunction "P_1") (pintype "passive"))
      (node (ref "PAD35") (pin "1") (pinfunction "P_1") (pintype "passive"))
      (node (ref "PAD36") (pin "1") (pinfunction "P_1") (pintype "passive"))
      (node (ref "PAD37") (pin "1") (pinfunction "P_1") (pintype "passive"))
      (node (ref "PAD38") (pin "1") (pinfunction "P_1") (pintype "passive"))
      (node (ref "PAD39") (pin "1") (pinfunction "P_1") (pintype "passive"))
      (node (ref "PAD40") (pin "1") (pinfunction "P_1") (pintype "passive"))
      (node (ref "PAD41") (pin "1") (pinfunction "P_1") (pintype "passive"))
      (node (ref "PAD42") (pin "1") (pinfunction "P_1") (pintype "passive"))
      (node (ref "PAD43") (pin "1") (pinfunction "P_1") (pintype "passive"))
      (node (ref "PAD44") (pin "1") (pinfunction "P_1") (pintype "passive"))
      (node (ref "U$3") (pin "N2") (pinfunction "1_N2") (pintype "bidirectional"))
    )
    (net (code "8") (name "Net-(PAD107-P)") (class "Default")
      (node (ref "PAD107") (pin "1") (pinfunction "P_1") (pintype "passive"))
      (node (ref "PAD108") (pin "1") (pinfunction "P_1") (pintype "passive"))
      (node (ref "PAD23") (pin "1") (pinfunction "P_1") (pintype "passive"))
      (node (ref "PAD24") (pin "1") (pinfunction "P_1") (pintype "passive"))
      (node (ref "PAD25") (pin "1") (pinfunction "P_1") (pintype "passive"))
      (node (ref "PAD26") (pin "1") (pinfunction "P_1") (pintype "passive"))
      (node (ref "PAD27") (pin "1") (pinfunction "P_1") (pintype "passive"))
      (node (ref "PAD28") (pin "1") (pinfunction "P_1") (pintype "passive"))
      (node (ref "PAD29") (pin "1") (pinfunction "P_1") (pintype "passive"))
      (node (ref "PAD30") (pin "1") (pinfunction "P_1") (pintype "passive"))
      (node (ref "PAD31") (pin "1") (pinfunction "P_1") (pintype "passive"))
      (node (ref "PAD32") (pin "1") (pinfunction "P_1") (pintype "passive"))
      (node (ref "PAD33") (pin "1") (pinfunction "P_1") (pintype "passive"))
      (node (ref "U$3") (pin "R2") (pinfunction "1_R2") (pintype "bidirectional"))
    )
    (net (code "9") (name "Net-(PAD109-P)") (class "Default")
      (node (ref "PAD109") (pin "1") (pinfunction "P_1") (pintype "passive"))
      (node (ref "PAD110") (pin "1") (pinfunction "P_1") (pintype "passive"))
      (node (ref "PAD12") (pin "1") (pinfunction "P_1") (pintype "passive"))
      (node (ref "PAD13") (pin "1") (pinfunction "P_1") (pintype "passive"))
      (node (ref "PAD14") (pin "1") (pinfunction "P_1") (pintype "passive"))
      (node (ref "PAD15") (pin "1") (pinfunction "P_1") (pintype "passive"))
      (node (ref "PAD16") (pin "1") (pinfunction "P_1") (pintype "passive"))
      (node (ref "PAD17") (pin "1") (pinfunction "P_1") (pintype "passive"))
      (node (ref "PAD18") (pin "1") (pinfunction "P_1") (pintype "passive"))
      (node (ref "PAD19") (pin "1") (pinfunction "P_1") (pintype "passive"))
      (node (ref "PAD20") (pin "1") (pinfunction "P_1") (pintype "passive"))
      (node (ref "PAD21") (pin "1") (pinfunction "P_1") (pintype "passive"))
      (node (ref "PAD22") (pin "1") (pinfunction "P_1") (pintype "passive"))
      (node (ref "U$3") (pin "T2") (pinfunction "1_T2") (pintype "bidirectional"))
    )
    (net (code "10") (name "Net-(PAD113-P)") (class "Default")
      (node (ref "PAD113") (pin "1") (pinfunction "P_1") (pintype "passive"))
      (node (ref "PAD114") (pin "1") (pinfunction "P_1") (pintype "passive"))
      (node (ref "PAD115") (pin "1") (pinfunction "P_1") (pintype "passive"))
      (node (ref "PAD116") (pin "1") (pinfunction "P_1") (pintype "passive"))
      (node (ref "PAD117") (pin "1") (pinfunction "P_1") (pintype "passive"))
      (node (ref "PAD118") (pin "1") (pinfunction "P_1") (pintype "passive"))
      (node (ref "PAD119") (pin "1") (pinfunction "P_1") (pintype "passive"))
      (node (ref "PAD120") (pin "1") (pinfunction "P_1") (pintype "passive"))
      (node (ref "U$3") (pin "S2") (pinfunction "1_S2") (pintype "bidirectional"))
    )
    (net (code "11") (name "Net-(PAD121-P)") (class "Default")
      (node (ref "PAD121") (pin "1") (pinfunction "P_1") (pintype "passive"))
      (node (ref "PAD122") (pin "1") (pinfunction "P_1") (pintype "passive"))
      (node (ref "PAD123") (pin "1") (pinfunction "P_1") (pintype "passive"))
      (node (ref "PAD124") (pin "1") (pinfunction "P_1") (pintype "passive"))
      (node (ref "PAD125") (pin "1") (pinfunction "P_1") (pintype "passive"))
      (node (ref "PAD126") (pin "1") (pinfunction "P_1") (pintype "passive"))
      (node (ref "PAD127") (pin "1") (pinfunction "P_1") (pintype "passive"))
      (node (ref "PAD128") (pin "1") (pinfunction "P_1") (pintype "passive"))
      (node (ref "U$3") (pin "P2") (pinfunction "1_P2") (pintype "bidirectional"))
    )
    (net (code "12") (name "Net-(PAD129-P)") (class "Default")
      (node (ref "PAD129") (pin "1") (pinfunction "P_1") (pintype "passive"))
      (node (ref "PAD130") (pin "1") (pinfunction "P_1") (pintype "passive"))
      (node (ref "PAD131") (pin "1") (pinfunction "P_1") (pintype "passive"))
      (node (ref "PAD132") (pin "1") (pinfunction "P_1") (pintype "passive"))
      (node (ref "PAD133") (pin "1") (pinfunction "P_1") (pintype "passive"))
      (node (ref "PAD134") (pin "1") (pinfunction "P_1") (pintype "passive"))
      (node (ref "PAD135") (pin "1") (pinfunction "P_1") (pintype "passive"))
      (node (ref "PAD136") (pin "1") (pinfunction "P_1") (pintype "passive"))
      (node (ref "U$3") (pin "M2") (pinfunction "1_M2") (pintype "bidirectional"))
    )
    (net (code "13") (name "Net-(PAD137-P)") (class "Default")
      (node (ref "PAD137") (pin "1") (pinfunction "P_1") (pintype "passive"))
      (node (ref "PAD138") (pin "1") (pinfunction "P_1") (pintype "passive"))
      (node (ref "PAD139") (pin "1") (pinfunction "P_1") (pintype "passive"))
      (node (ref "PAD140") (pin "1") (pinfunction "P_1") (pintype "passive"))
      (node (ref "PAD141") (pin "1") (pinfunction "P_1") (pintype "passive"))
      (node (ref "PAD142") (pin "1") (pinfunction "P_1") (pintype "passive"))
      (node (ref "PAD143") (pin "1") (pinfunction "P_1") (pintype "passive"))
      (node (ref "PAD144") (pin "1") (pinfunction "P_1") (pintype "passive"))
      (node (ref "U$3") (pin "K2") (pinfunction "1_K2") (pintype "bidirectional"))
    )
    (net (code "14") (name "Net-(PAD145-P)") (class "Default")
      (node (ref "PAD145") (pin "1") (pinfunction "P_1") (pintype "passive"))
      (node (ref "PAD146") (pin "1") (pinfunction "P_1") (pintype "passive"))
      (node (ref "PAD147") (pin "1") (pinfunction "P_1") (pintype "passive"))
      (node (ref "PAD148") (pin "1") (pinfunction "P_1") (pintype "passive"))
      (node (ref "PAD149") (pin "1") (pinfunction "P_1") (pintype "passive"))
      (node (ref "PAD150") (pin "1") (pinfunction "P_1") (pintype "passive"))
      (node (ref "PAD151") (pin "1") (pinfunction "P_1") (pintype "passive"))
      (node (ref "PAD152") (pin "1") (pinfunction "P_1") (pintype "passive"))
      (node (ref "U$3") (pin "H2") (pinfunction "1_H2") (pintype "bidirectional"))
    )
    (net (code "15") (name "Net-(PAD153-P)") (class "Default")
      (node (ref "PAD153") (pin "1") (pinfunction "P_1") (pintype "passive"))
      (node (ref "PAD154") (pin "1") (pinfunction "P_1") (pintype "passive"))
      (node (ref "PAD155") (pin "1") (pinfunction "P_1") (pintype "passive"))
      (node (ref "PAD156") (pin "1") (pinfunction "P_1") (pintype "passive"))
      (node (ref "PAD157") (pin "1") (pinfunction "P_1") (pintype "passive"))
      (node (ref "PAD158") (pin "1") (pinfunction "P_1") (pintype "passive"))
      (node (ref "PAD159") (pin "1") (pinfunction "P_1") (pintype "passive"))
      (node (ref "PAD160") (pin "1") (pinfunction "P_1") (pintype "passive"))
      (node (ref "U$3") (pin "E2") (pinfunction "1_E2") (pintype "bidirectional"))
    )
    (net (code "16") (name "Net-(PAD161-P)") (class "Default")
      (node (ref "PAD161") (pin "1") (pinfunction "P_1") (pintype "passive"))
      (node (ref "PAD162") (pin "1") (pinfunction "P_1") (pintype "passive"))
      (node (ref "PAD163") (pin "1") (pinfunction "P_1") (pintype "passive"))
      (node (ref "PAD164") (pin "1") (pinfunction "P_1") (pintype "passive"))
      (node (ref "PAD165") (pin "1") (pinfunction "P_1") (pintype "passive"))
      (node (ref "PAD166") (pin "1") (pinfunction "P_1") (pintype "passive"))
      (node (ref "PAD167") (pin "1") (pinfunction "P_1") (pintype "passive"))
      (node (ref "PAD168") (pin "1") (pinfunction "P_1") (pintype "passive"))
      (node (ref "U$3") (pin "C2") (pinfunction "1_C2") (pintype "bidirectional"))
    )
    (net (code "17") (name "Net-(PAD169-P)") (class "Default")
      (node (ref "PAD169") (pin "1") (pinfunction "P_1") (pintype "passive"))
      (node (ref "PAD170") (pin "1") (pinfunction "P_1") (pintype "passive"))
      (node (ref "PAD171") (pin "1") (pinfunction "P_1") (pintype "passive"))
      (node (ref "PAD172") (pin "1") (pinfunction "P_1") (pintype "passive"))
      (node (ref "PAD173") (pin "1") (pinfunction "P_1") (pintype "passive"))
      (node (ref "PAD174") (pin "1") (pinfunction "P_1") (pintype "passive"))
      (node (ref "PAD175") (pin "1") (pinfunction "P_1") (pintype "passive"))
      (node (ref "PAD176") (pin "1") (pinfunction "P_1") (pintype "passive"))
      (node (ref "U$3") (pin "B2") (pinfunction "1_B2") (pintype "bidirectional"))
    )
    (net (code "18") (name "Net-(PAD177-P)") (class "Default")
      (node (ref "PAD177") (pin "1") (pinfunction "P_1") (pintype "passive"))
      (node (ref "PAD178") (pin "1") (pinfunction "P_1") (pintype "passive"))
      (node (ref "PAD179") (pin "1") (pinfunction "P_1") (pintype "passive"))
      (node (ref "PAD180") (pin "1") (pinfunction "P_1") (pintype "passive"))
      (node (ref "PAD181") (pin "1") (pinfunction "P_1") (pintype "passive"))
      (node (ref "PAD182") (pin "1") (pinfunction "P_1") (pintype "passive"))
      (node (ref "PAD183") (pin "1") (pinfunction "P_1") (pintype "passive"))
      (node (ref "PAD184") (pin "1") (pinfunction "P_1") (pintype "passive"))
      (node (ref "U$3") (pin "A2") (pinfunction "1_A2") (pintype "bidirectional"))
    )
  )
)
